# BAT.net
KiCad netlist of a schematic drawn in Altium Designer
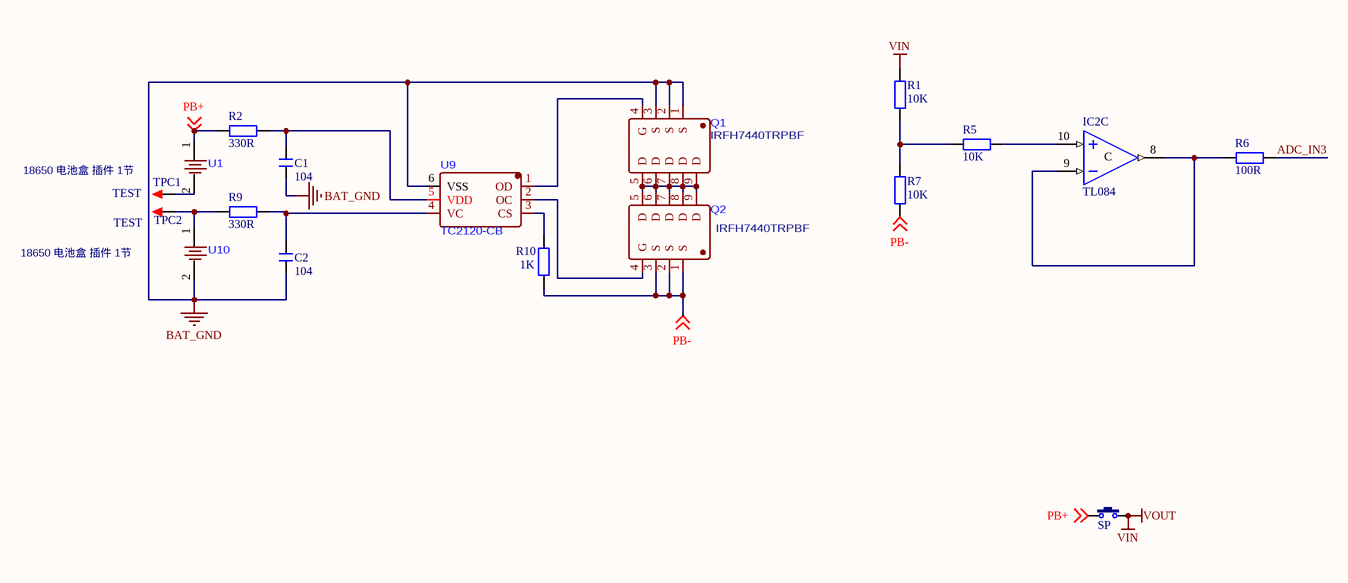
[diagram p0: BAT.SchDoc]

(export (version "E")
  (design (tool "Eeschema 10.0.6"))
  (components
    (comp (ref "C1")
      (value "104")
      (footprint "C 0805_L")
      (description "无极性贴片电容")
      (fields (field (name "版权归属") "源创客"))
      (libsource (lib "3.1   - 电阻-电容-电感") (part "C"))
    )
    (comp (ref "C2")
      (value "104")
      (footprint "C 0805_L")
      (description "无极性贴片电容")
      (fields (field (name "版权归属") "源创客"))
      (libsource (lib "3.1   - 电阻-电容-电感") (part "C"))
    )
    (comp (ref "IC2")
      (value "TL084")
      (footprint "SOP14_N")
      (description "4路运放")
      (fields (field (name "版权归属") "源创客"))
      (libsource (lib "1.5   - 运放-功放") (part "TL084"))
    )
    (comp (ref "Q1")
      (value "IRFH7440TRPBF")
      (footprint "PQFN-8P_L5.8-W4.9-P1.27-LS6.0-BL")
      (libsource (lib "IRFH7440TRPBF") (part "IRFH7440TRPBF"))
    )
    (comp (ref "Q2")
      (value "IRFH7440TRPBF")
      (footprint "PQFN-8P_L5.8-W4.9-P1.27-LS6.0-BL")
      (libsource (lib "IRFH7440TRPBF") (part "IRFH7440TRPBF"))
    )
    (comp (ref "R1")
      (value "10K")
      (footprint "R 0805_L")
      (description "贴片电阻")
      (fields (field (name "版权归属") "源创客"))
      (libsource (lib "3.1   - 电阻-电容-电感") (part "R"))
    )
    (comp (ref "R2")
      (value "330R")
      (footprint "R 0805_L")
      (description "贴片电阻")
      (fields (field (name "版权归属") "源创客"))
      (libsource (lib "3.1   - 电阻-电容-电感") (part "R"))
    )
    (comp (ref "R5")
      (value "10K")
      (footprint "R 0805_L")
      (description "贴片电阻")
      (fields (field (name "版权归属") "源创客"))
      (libsource (lib "3.1   - 电阻-电容-电感") (part "R"))
    )
    (comp (ref "R6")
      (value "100R")
      (footprint "R 0805_L")
      (description "贴片电阻")
      (fields (field (name "版权归属") "源创客"))
      (libsource (lib "3.1   - 电阻-电容-电感") (part "R"))
    )
    (comp (ref "R7")
      (value "10K")
      (footprint "R 0805_L")
      (description "贴片电阻")
      (fields (field (name "版权归属") "源创客"))
      (libsource (lib "3.1   - 电阻-电容-电感") (part "R"))
    )
    (comp (ref "R9")
      (value "330R")
      (footprint "R 0805_L")
      (description "贴片电阻")
      (fields (field (name "版权归属") "源创客"))
      (libsource (lib "3.1   - 电阻-电容-电感") (part "R"))
    )
    (comp (ref "R10")
      (value "1K")
      (footprint "R 0805_L")
      (description "贴片电阻")
      (fields (field (name "版权归属") "源创客"))
      (libsource (lib "3.1   - 电阻-电容-电感") (part "R"))
    )
    (comp (ref "SP")
      (value "6x6x5")
      (footprint "KEY-TH_CN-KCD11")
      (description "2脚直插6x6轻触开关")
      (fields (field (name "版权归属") "源创客"))
      (libsource (lib "5.1   - 按键-开关") (part "TSW DIP-2Pin-6x6"))
    )
    (comp (ref "TPC1")
      (value "TEST")
      (footprint "TEST 1.6")
      (description "测试点")
      (fields (field (name "版权归属") "源创客"))
      (libsource (lib "15.1 - 未分类器件") (part "TEST"))
    )
    (comp (ref "TPC2")
      (value "TEST")
      (footprint "TEST 1.6")
      (description "测试点")
      (fields (field (name "版权归属") "源创客"))
      (libsource (lib "15.1 - 未分类器件") (part "TEST"))
    )
    (comp (ref "U1")
      (value "18650 电池盒 插件 1节")
      (footprint "BAT-TH_18650-C9900004923")
      (libsource (lib "18650 电池盒 插件 1节") (part "18650 电池盒 插件 1节"))
    )
    (comp (ref "U9")
      (value "TC2120-CB")
      (footprint "SOT23-6L")
      (libsource (lib "TC2120-CB") (part "TC2120-CB"))
    )
    (comp (ref "U10")
      (value "18650 电池盒 插件 1节")
      (footprint "BAT-TH_18650-C9900004923")
      (libsource (lib "18650 电池盒 插件 1节") (part "18650 电池盒 插件 1节"))
    )
  )
  (nets
    (net (code "1") (name "/ADC_IN3") (class "Default")
      (node (ref "R6") (pin "1") (pinfunction "1_1") (pintype "passive"))
    )
    (net (code "2") (name "BAT_GND") (class "Default")
      (node (ref "C1") (pin "1") (pinfunction "1_1") (pintype "passive"))
      (node (ref "C2") (pin "1") (pinfunction "1_1") (pintype "passive"))
      (node (ref "Q1") (pin "1") (pinfunction "S_1") (pintype "passive"))
      (node (ref "Q1") (pin "2") (pinfunction "S_2") (pintype "passive"))
      (node (ref "Q1") (pin "3") (pinfunction "S_3") (pintype "passive"))
      (node (ref "U10") (pin "2") (pinfunction "2_2") (pintype "passive"))
      (node (ref "U9") (pin "6") (pinfunction "VSS_6") (pintype "passive"))
    )
    (net (code "3") (name "Net-(IC2C-IN+)") (class "Default")
      (node (ref "IC2") (pin "10") (pinfunction "IN+_10") (pintype "input"))
      (node (ref "R5") (pin "1") (pinfunction "1_1") (pintype "passive"))
    )
    (net (code "4") (name "Net-(IC2C-IN-)") (class "Default")
      (node (ref "IC2") (pin "8") (pinfunction "OUT_8") (pintype "output"))
      (node (ref "IC2") (pin "9") (pinfunction "IN-_9") (pintype "input"))
      (node (ref "R6") (pin "2") (pinfunction "2_2") (pintype "passive"))
    )
    (net (code "5") (name "Net-(Q1-D-Pad5)") (class "Default")
      (node (ref "Q1") (pin "5") (pinfunction "D_5") (pintype "passive"))
      (node (ref "Q1") (pin "6") (pinfunction "D_6") (pintype "passive"))
      (node (ref "Q1") (pin "7") (pinfunction "D_7") (pintype "passive"))
      (node (ref "Q1") (pin "8") (pinfunction "D_8") (pintype "passive"))
      (node (ref "Q1") (pin "9") (pinfunction "D_9") (pintype "passive"))
      (node (ref "Q2") (pin "5") (pinfunction "D_5") (pintype "passive"))
      (node (ref "Q2") (pin "6") (pinfunction "D_6") (pintype "passive"))
      (node (ref "Q2") (pin "7") (pinfunction "D_7") (pintype "passive"))
      (node (ref "Q2") (pin "8") (pinfunction "D_8") (pintype "passive"))
      (node (ref "Q2") (pin "9") (pinfunction "D_9") (pintype "passive"))
    )
    (net (code "6") (name "Net-(Q1-G)") (class "Default")
      (node (ref "Q1") (pin "4") (pinfunction "G_4") (pintype "passive"))
      (node (ref "U9") (pin "1") (pinfunction "OD_1") (pintype "passive"))
    )
    (net (code "7") (name "Net-(Q2-G)") (class "Default")
      (node (ref "Q2") (pin "4") (pinfunction "G_4") (pintype "passive"))
      (node (ref "U9") (pin "2") (pinfunction "OC_2") (pintype "passive"))
    )
    (net (code "8") (name "Net-(R1-Pad2)") (class "Default")
      (node (ref "R1") (pin "2") (pinfunction "2_2") (pintype "passive"))
      (node (ref "R5") (pin "2") (pinfunction "2_2") (pintype "passive"))
      (node (ref "R7") (pin "1") (pinfunction "1_1") (pintype "passive"))
    )
    (net (code "9") (name "Net-(R9-Pad2)") (class "Default")
      (node (ref "R9") (pin "2") (pinfunction "2_2") (pintype "passive"))
      (node (ref "TPC2") (pin "1") (pinfunction "1_1") (pintype "passive"))
      (node (ref "U10") (pin "1") (pinfunction "1_1") (pintype "passive"))
    )
    (net (code "10") (name "Net-(TPC1-Pad1)") (class "Default")
      (node (ref "TPC1") (pin "1") (pinfunction "1_1") (pintype "passive"))
      (node (ref "U1") (pin "2") (pinfunction "2_2") (pintype "passive"))
    )
    (net (code "11") (name "Net-(U9-CS)") (class "Default")
      (node (ref "R10") (pin "1") (pinfunction "1_1") (pintype "passive"))
      (node (ref "U9") (pin "3") (pinfunction "CS_3") (pintype "passive"))
    )
    (net (code "12") (name "Net-(U9-VC)") (class "Default")
      (node (ref "C2") (pin "2") (pinfunction "2_2") (pintype "passive"))
      (node (ref "R9") (pin "1") (pinfunction "1_1") (pintype "passive"))
      (node (ref "U9") (pin "4") (pinfunction "VC_4") (pintype "passive"))
    )
    (net (code "13") (name "Net-(U9-VDD)") (class "Default")
      (node (ref "C1") (pin "2") (pinfunction "2_2") (pintype "passive"))
      (node (ref "R2") (pin "1") (pinfunction "1_1") (pintype "passive"))
      (node (ref "U9") (pin "5") (pinfunction "VDD_5") (pintype "passive"))
    )
    (net (code "14") (name "PB+") (class "Default")
      (node (ref "R2") (pin "2") (pinfunction "2_2") (pintype "passive"))
      (node (ref "SP") (pin "1") (pinfunction "1_1") (pintype "passive"))
      (node (ref "U1") (pin "1") (pinfunction "1_1") (pintype "passive"))
    )
    (net (code "15") (name "PB-") (class "Default")
      (node (ref "Q2") (pin "1") (pinfunction "S_1") (pintype "passive"))
      (node (ref "Q2") (pin "2") (pinfunction "S_2") (pintype "passive"))
      (node (ref "Q2") (pin "3") (pinfunction "S_3") (pintype "passive"))
      (node (ref "R10") (pin "2") (pinfunction "2_2") (pintype "passive"))
      (node (ref "R7") (pin "2") (pinfunction "2_2") (pintype "passive"))
    )
    (net (code "16") (name "VIN") (class "Default")
      (node (ref "R1") (pin "1") (pinfunction "1_1") (pintype "passive"))
      (node (ref "SP") (pin "2") (pinfunction "2_2") (pintype "passive"))
    )
  )
)
